# ProPrj_ESP32-S3-DEVKIT_Sensor_Project_20.net
KiCad netlist of a schematic drawn in EasyEDA Pro
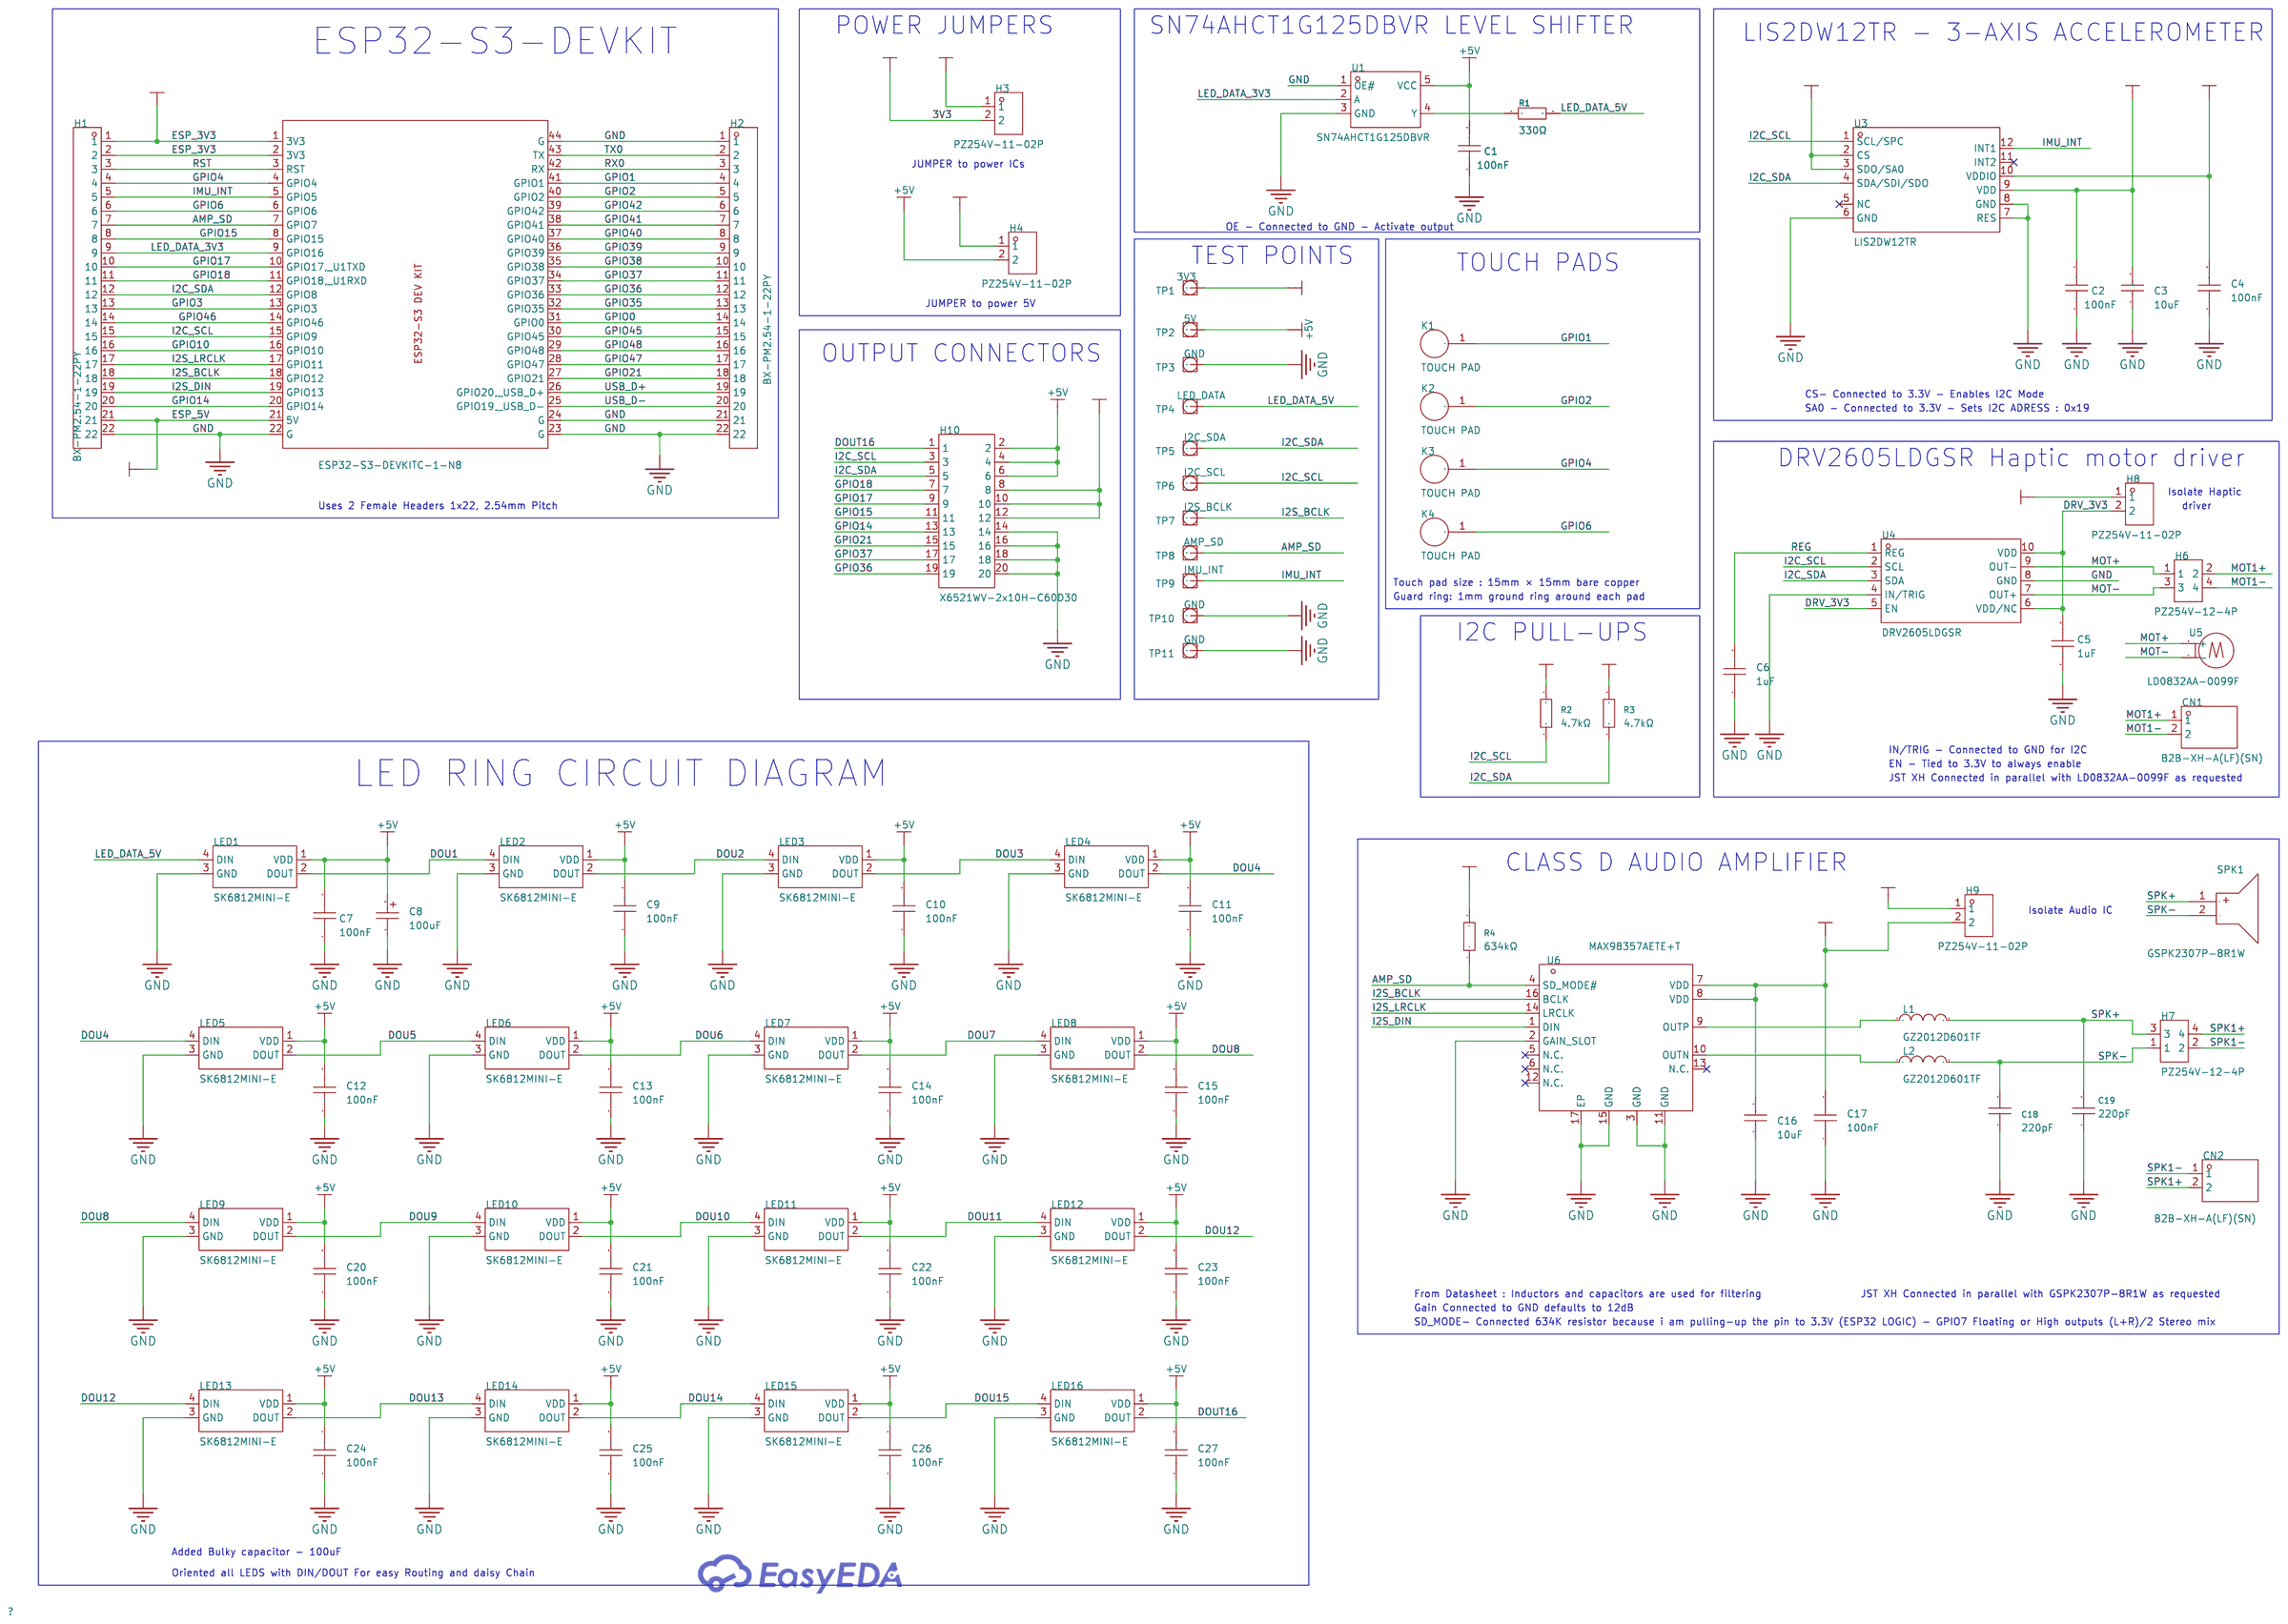
[diagram p0: schematic sheet]

(export (version "E")
  (design (tool "Eeschema 10.0.6"))
  (components
    (comp (ref "C1")
      (value "100nF")
      (footprint "easyedapro:C0402")
      (description "Capacitance:100nF Tolerance:±10% Tolerance:±10% Voltage Rating:16V Temperature Coefficient:X7R")
      (fields
        (field (name "Manufacturer Part") "CL05B104KO5NNNC")
        (field (name "Manufacturer") "SAMSUNG(三星)")
      )
      (libsource (lib "easyedapro") (part "CL05B104KO5NNNC"))
    )
    (comp (ref "C2")
      (value "100nF")
      (footprint "easyedapro:C0402")
      (description "Capacitance:100nF Tolerance:±10% Tolerance:±10% Voltage Rating:16V Temperature Coefficient:X7R")
      (fields
        (field (name "Manufacturer Part") "CL05B104KO5NNNC")
        (field (name "Manufacturer") "SAMSUNG(三星)")
      )
      (libsource (lib "easyedapro") (part "CL05B104KO5NNNC"))
    )
    (comp (ref "C3")
      (value "10uF")
      (footprint "easyedapro:C0402")
      (description "Capacitance:10uF Tolerance:±20% Tolerance:±20% Voltage Rating:6.3V Temperature Coefficient:X5R")
      (fields
        (field (name "Manufacturer Part") "CL05A106MQ5NUNC")
        (field (name "Manufacturer") "SAMSUNG(三星)")
      )
      (libsource (lib "easyedapro") (part "CL05A106MQ5NUNC"))
    )
    (comp (ref "C4")
      (value "100nF")
      (footprint "easyedapro:C0402")
      (description "Capacitance:100nF Tolerance:±10% Tolerance:±10% Voltage Rating:16V Temperature Coefficient:X7R")
      (fields
        (field (name "Manufacturer Part") "CL05B104KO5NNNC")
        (field (name "Manufacturer") "SAMSUNG(三星)")
      )
      (libsource (lib "easyedapro") (part "CL05B104KO5NNNC"))
    )
    (comp (ref "C5")
      (value "1uF")
      (footprint "easyedapro:C0402")
      (description "Capacitance:1uF Tolerance:±10% Tolerance:±10% Voltage Rating:25V Temperature Coefficient:X5R")
      (fields
        (field (name "Manufacturer Part") "CL05A105KA5NQNC")
        (field (name "Manufacturer") "SAMSUNG(三星)")
      )
      (libsource (lib "easyedapro") (part "CL05A105KA5NQNC"))
    )
    (comp (ref "C6")
      (value "1uF")
      (footprint "easyedapro:C0402")
      (description "Capacitance:1uF Tolerance:±10% Tolerance:±10% Voltage Rating:25V Temperature Coefficient:X5R")
      (fields
        (field (name "Manufacturer Part") "CL05A105KA5NQNC")
        (field (name "Manufacturer") "SAMSUNG(三星)")
      )
      (libsource (lib "easyedapro") (part "CL05A105KA5NQNC"))
    )
    (comp (ref "C7")
      (value "100nF")
      (footprint "easyedapro:C0402")
      (description "Capacitance:100nF Tolerance:±10% Tolerance:±10% Voltage Rating:16V Temperature Coefficient:X7R")
      (fields
        (field (name "Manufacturer Part") "CL05B104KO5NNNC")
        (field (name "Manufacturer") "SAMSUNG(三星)")
      )
      (libsource (lib "easyedapro") (part "CL05B104KO5NNNC"))
    )
    (comp (ref "C8")
      (value "100uF")
      (footprint "easyedapro:CASE-B_3528")
      (fields (field (name "Manufacturer Part") "TAJB107M010RNJ") (field (name "Manufacturer") "Kyocera AVX"))
      (libsource (lib "easyedapro") (part "TAJB107M010RNJ"))
    )
    (comp (ref "C9")
      (value "100nF")
      (footprint "easyedapro:C0402")
      (description "Capacitance:100nF Tolerance:±10% Tolerance:±10% Voltage Rating:16V Temperature Coefficient:X7R")
      (fields
        (field (name "Manufacturer Part") "CL05B104KO5NNNC")
        (field (name "Manufacturer") "SAMSUNG(三星)")
      )
      (libsource (lib "easyedapro") (part "CL05B104KO5NNNC"))
    )
    (comp (ref "C10")
      (value "100nF")
      (footprint "easyedapro:C0402")
      (description "Capacitance:100nF Tolerance:±10% Tolerance:±10% Voltage Rating:16V Temperature Coefficient:X7R")
      (fields
        (field (name "Manufacturer Part") "CL05B104KO5NNNC")
        (field (name "Manufacturer") "SAMSUNG(三星)")
      )
      (libsource (lib "easyedapro") (part "CL05B104KO5NNNC"))
    )
    (comp (ref "C11")
      (value "100nF")
      (footprint "easyedapro:C0402")
      (description "Capacitance:100nF Tolerance:±10% Tolerance:±10% Voltage Rating:16V Temperature Coefficient:X7R")
      (fields
        (field (name "Manufacturer Part") "CL05B104KO5NNNC")
        (field (name "Manufacturer") "SAMSUNG(三星)")
      )
      (libsource (lib "easyedapro") (part "CL05B104KO5NNNC"))
    )
    (comp (ref "C12")
      (value "100nF")
      (footprint "easyedapro:C0402")
      (description "Capacitance:100nF Tolerance:±10% Tolerance:±10% Voltage Rating:16V Temperature Coefficient:X7R")
      (fields
        (field (name "Manufacturer Part") "CL05B104KO5NNNC")
        (field (name "Manufacturer") "SAMSUNG(三星)")
      )
      (libsource (lib "easyedapro") (part "CL05B104KO5NNNC"))
    )
    (comp (ref "C13")
      (value "100nF")
      (footprint "easyedapro:C0402")
      (description "Capacitance:100nF Tolerance:±10% Tolerance:±10% Voltage Rating:16V Temperature Coefficient:X7R")
      (fields
        (field (name "Manufacturer Part") "CL05B104KO5NNNC")
        (field (name "Manufacturer") "SAMSUNG(三星)")
      )
      (libsource (lib "easyedapro") (part "CL05B104KO5NNNC"))
    )
    (comp (ref "C14")
      (value "100nF")
      (footprint "easyedapro:C0402")
      (description "Capacitance:100nF Tolerance:±10% Tolerance:±10% Voltage Rating:16V Temperature Coefficient:X7R")
      (fields
        (field (name "Manufacturer Part") "CL05B104KO5NNNC")
        (field (name "Manufacturer") "SAMSUNG(三星)")
      )
      (libsource (lib "easyedapro") (part "CL05B104KO5NNNC"))
    )
    (comp (ref "C15")
      (value "100nF")
      (footprint "easyedapro:C0402")
      (description "Capacitance:100nF Tolerance:±10% Tolerance:±10% Voltage Rating:16V Temperature Coefficient:X7R")
      (fields
        (field (name "Manufacturer Part") "CL05B104KO5NNNC")
        (field (name "Manufacturer") "SAMSUNG(三星)")
      )
      (libsource (lib "easyedapro") (part "CL05B104KO5NNNC"))
    )
    (comp (ref "C16")
      (value "10uF")
      (footprint "easyedapro:C0402")
      (description "Capacitance:10uF Tolerance:±20% Tolerance:±20% Voltage Rating:6.3V Temperature Coefficient:X5R")
      (fields
        (field (name "Manufacturer Part") "CL05A106MQ5NUNC")
        (field (name "Manufacturer") "SAMSUNG(三星)")
      )
      (libsource (lib "easyedapro") (part "CL05A106MQ5NUNC"))
    )
    (comp (ref "C17")
      (value "100nF")
      (footprint "easyedapro:C0402")
      (description "Capacitance:100nF Tolerance:±10% Tolerance:±10% Voltage Rating:16V Temperature Coefficient:X7R")
      (fields
        (field (name "Manufacturer Part") "CL05B104KO5NNNC")
        (field (name "Manufacturer") "SAMSUNG(三星)")
      )
      (libsource (lib "easyedapro") (part "CL05B104KO5NNNC"))
    )
    (comp (ref "C18")
      (value "220pF")
      (footprint "easyedapro:C0603")
      (description "Capacitance:220pF Tolerance:±10% Tolerance:±10% Voltage Rating:50V Temperature Coefficient:X7R")
      (fields
        (field (name "Manufacturer Part") "CL10B221KB8NNNC")
        (field (name "Manufacturer") "SAMSUNG(三星)")
      )
      (libsource (lib "easyedapro") (part "CL10B221KB8NNNC"))
    )
    (comp (ref "C19")
      (value "220pF")
      (footprint "easyedapro:C0603")
      (description "Capacitance:220pF Tolerance:±10% Tolerance:±10% Voltage Rating:50V Temperature Coefficient:X7R")
      (fields
        (field (name "Manufacturer Part") "CL10B221KB8NNNC")
        (field (name "Manufacturer") "SAMSUNG(三星)")
      )
      (libsource (lib "easyedapro") (part "CL10B221KB8NNNC"))
    )
    (comp (ref "C20")
      (value "100nF")
      (footprint "easyedapro:C0402")
      (description "Capacitance:100nF Tolerance:±10% Tolerance:±10% Voltage Rating:16V Temperature Coefficient:X7R")
      (fields
        (field (name "Manufacturer Part") "CL05B104KO5NNNC")
        (field (name "Manufacturer") "SAMSUNG(三星)")
      )
      (libsource (lib "easyedapro") (part "CL05B104KO5NNNC"))
    )
    (comp (ref "C21")
      (value "100nF")
      (footprint "easyedapro:C0402")
      (description "Capacitance:100nF Tolerance:±10% Tolerance:±10% Voltage Rating:16V Temperature Coefficient:X7R")
      (fields
        (field (name "Manufacturer Part") "CL05B104KO5NNNC")
        (field (name "Manufacturer") "SAMSUNG(三星)")
      )
      (libsource (lib "easyedapro") (part "CL05B104KO5NNNC"))
    )
    (comp (ref "C22")
      (value "100nF")
      (footprint "easyedapro:C0402")
      (description "Capacitance:100nF Tolerance:±10% Tolerance:±10% Voltage Rating:16V Temperature Coefficient:X7R")
      (fields
        (field (name "Manufacturer Part") "CL05B104KO5NNNC")
        (field (name "Manufacturer") "SAMSUNG(三星)")
      )
      (libsource (lib "easyedapro") (part "CL05B104KO5NNNC"))
    )
    (comp (ref "C23")
      (value "100nF")
      (footprint "easyedapro:C0402")
      (description "Capacitance:100nF Tolerance:±10% Tolerance:±10% Voltage Rating:16V Temperature Coefficient:X7R")
      (fields
        (field (name "Manufacturer Part") "CL05B104KO5NNNC")
        (field (name "Manufacturer") "SAMSUNG(三星)")
      )
      (libsource (lib "easyedapro") (part "CL05B104KO5NNNC"))
    )
    (comp (ref "C24")
      (value "100nF")
      (footprint "easyedapro:C0402")
      (description "Capacitance:100nF Tolerance:±10% Tolerance:±10% Voltage Rating:16V Temperature Coefficient:X7R")
      (fields
        (field (name "Manufacturer Part") "CL05B104KO5NNNC")
        (field (name "Manufacturer") "SAMSUNG(三星)")
      )
      (libsource (lib "easyedapro") (part "CL05B104KO5NNNC"))
    )
    (comp (ref "C25")
      (value "100nF")
      (footprint "easyedapro:C0402")
      (description "Capacitance:100nF Tolerance:±10% Tolerance:±10% Voltage Rating:16V Temperature Coefficient:X7R")
      (fields
        (field (name "Manufacturer Part") "CL05B104KO5NNNC")
        (field (name "Manufacturer") "SAMSUNG(三星)")
      )
      (libsource (lib "easyedapro") (part "CL05B104KO5NNNC"))
    )
    (comp (ref "C26")
      (value "100nF")
      (footprint "easyedapro:C0402")
      (description "Capacitance:100nF Tolerance:±10% Tolerance:±10% Voltage Rating:16V Temperature Coefficient:X7R")
      (fields
        (field (name "Manufacturer Part") "CL05B104KO5NNNC")
        (field (name "Manufacturer") "SAMSUNG(三星)")
      )
      (libsource (lib "easyedapro") (part "CL05B104KO5NNNC"))
    )
    (comp (ref "C27")
      (value "100nF")
      (footprint "easyedapro:C0402")
      (description "Capacitance:100nF Tolerance:±10% Tolerance:±10% Voltage Rating:16V Temperature Coefficient:X7R")
      (fields
        (field (name "Manufacturer Part") "CL05B104KO5NNNC")
        (field (name "Manufacturer") "SAMSUNG(三星)")
      )
      (libsource (lib "easyedapro") (part "CL05B104KO5NNNC"))
    )
    (comp (ref "CN1")
      (value "B2B-XH-A(LF)(SN)")
      (footprint "easyedapro:CONN-TH_B2B-XH-A-LF-SN")
      (fields (field (name "Manufacturer") "JST"))
      (libsource (lib "easyedapro") (part "B2B-XH-A (LF)(SN)"))
    )
    (comp (ref "CN2")
      (value "B2B-XH-A(LF)(SN)")
      (footprint "easyedapro:CONN-TH_B2B-XH-A-LF-SN")
      (fields (field (name "Manufacturer") "JST"))
      (libsource (lib "easyedapro") (part "B2B-XH-A (LF)(SN)"))
    )
    (comp (ref "H1")
      (value "BX-PM2.54-1-22PY")
      (footprint "easyedapro:HDR-TH_22P-P2.54-V-F")
      (fields (field (name "Manufacturer") "Bossie(博锡)"))
      (libsource (lib "easyedapro") (part "BX-PM2.54-1-22PY"))
    )
    (comp (ref "H2")
      (value "BX-PM2.54-1-22PY")
      (footprint "easyedapro:HDR-TH_22P-P2.54-V-F")
      (fields (field (name "Manufacturer") "Bossie(博锡)"))
      (libsource (lib "easyedapro") (part "BX-PM2.54-1-22PY"))
    )
    (comp (ref "H3")
      (value "PZ254V-11-02P")
      (footprint "easyedapro:HDR-TH_2P-P2.54-V-M")
      (fields (field (name "Manufacturer") "XFCN"))
      (libsource (lib "easyedapro") (part "PZ254V-11-02P"))
    )
    (comp (ref "H4")
      (value "PZ254V-11-02P")
      (footprint "easyedapro:HDR-TH_2P-P2.54-V-M")
      (fields (field (name "Manufacturer") "XFCN"))
      (libsource (lib "easyedapro") (part "PZ254V-11-02P"))
    )
    (comp (ref "H6")
      (value "PZ254V-12-4P")
      (footprint "easyedapro:HDR-TH_4P-P2.54-V-M-R2-C2-S2.54")
      (fields (field (name "Manufacturer") "XFCN(兴飞)"))
      (libsource (lib "easyedapro") (part "PZ254V-12-4P"))
    )
    (comp (ref "H7")
      (value "PZ254V-12-4P")
      (footprint "easyedapro:HDR-TH_4P-P2.54-V-M-R2-C2-S2.54")
      (fields (field (name "Manufacturer") "XFCN(兴飞)"))
      (libsource (lib "easyedapro") (part "PZ254V-12-4P"))
    )
    (comp (ref "H8")
      (value "PZ254V-11-02P")
      (footprint "easyedapro:HDR-TH_2P-P2.54-V-M")
      (fields (field (name "Manufacturer") "XFCN"))
      (libsource (lib "easyedapro") (part "PZ254V-11-02P"))
    )
    (comp (ref "H9")
      (value "PZ254V-11-02P")
      (footprint "easyedapro:HDR-TH_2P-P2.54-V-M")
      (fields (field (name "Manufacturer") "XFCN"))
      (libsource (lib "easyedapro") (part "PZ254V-11-02P"))
    )
    (comp (ref "H10")
      (value "X6521WV-2x10H-C60D30")
      (footprint "easyedapro:HDR-TH_20P-P2.54-V-M-R2-C10-S2.54")
      (fields (field (name "Manufacturer") "XKB Connection(中国星坤)"))
      (libsource (lib "easyedapro") (part "X6521WV-2×10H-C30D60"))
    )
    (comp (ref "K1")
      (value "TOUCH PAD")
      (footprint "easyedapro:TOUCH_PAD")
      (fields (field (name "Manufacturer Part") "Touch"))
      (libsource (lib "easyedapro") (part "TOUCH PAD"))
    )
    (comp (ref "K2")
      (value "TOUCH PAD")
      (footprint "easyedapro:TOUCH_PAD")
      (fields (field (name "Manufacturer Part") "Touch"))
      (libsource (lib "easyedapro") (part "TOUCH PAD"))
    )
    (comp (ref "K3")
      (value "TOUCH PAD")
      (footprint "easyedapro:TOUCH_PAD")
      (fields (field (name "Manufacturer Part") "Touch"))
      (libsource (lib "easyedapro") (part "TOUCH PAD"))
    )
    (comp (ref "K4")
      (value "TOUCH PAD")
      (footprint "easyedapro:TOUCH_PAD")
      (fields (field (name "Manufacturer Part") "Touch"))
      (libsource (lib "easyedapro") (part "TOUCH PAD"))
    )
    (comp (ref "L1")
      (value "GZ2012D601TF")
      (footprint "easyedapro:L0805")
      (fields (field (name "Manufacturer") "Sunlord(顺络)"))
      (libsource (lib "easyedapro") (part "GZ2012D601TF"))
    )
    (comp (ref "L2")
      (value "GZ2012D601TF")
      (footprint "easyedapro:L0805")
      (fields (field (name "Manufacturer") "Sunlord(顺络)"))
      (libsource (lib "easyedapro") (part "GZ2012D601TF"))
    )
    (comp (ref "LED1")
      (value "SK6812MINI-E")
      (footprint "easyedapro:LED-SMD_L3.2-W2.8-LS5.9_SK6812MINI-E")
      (fields (field (name "Manufacturer") "欧思科光电"))
      (libsource (lib "easyedapro") (part "SK6812MINI-E_C5149201"))
    )
    (comp (ref "LED2")
      (value "SK6812MINI-E")
      (footprint "easyedapro:LED-SMD_L3.2-W2.8-LS5.9_SK6812MINI-E")
      (fields (field (name "Manufacturer") "欧思科光电"))
      (libsource (lib "easyedapro") (part "SK6812MINI-E_C5149201"))
    )
    (comp (ref "LED3")
      (value "SK6812MINI-E")
      (footprint "easyedapro:LED-SMD_L3.2-W2.8-LS5.9_SK6812MINI-E")
      (fields (field (name "Manufacturer") "欧思科光电"))
      (libsource (lib "easyedapro") (part "SK6812MINI-E_C5149201"))
    )
    (comp (ref "LED4")
      (value "SK6812MINI-E")
      (footprint "easyedapro:LED-SMD_L3.2-W2.8-LS5.9_SK6812MINI-E")
      (fields (field (name "Manufacturer") "欧思科光电"))
      (libsource (lib "easyedapro") (part "SK6812MINI-E_C5149201"))
    )
    (comp (ref "LED5")
      (value "SK6812MINI-E")
      (footprint "easyedapro:LED-SMD_L3.2-W2.8-LS5.9_SK6812MINI-E")
      (fields (field (name "Manufacturer") "欧思科光电"))
      (libsource (lib "easyedapro") (part "SK6812MINI-E_C5149201"))
    )
    (comp (ref "LED6")
      (value "SK6812MINI-E")
      (footprint "easyedapro:LED-SMD_L3.2-W2.8-LS5.9_SK6812MINI-E")
      (fields (field (name "Manufacturer") "欧思科光电"))
      (libsource (lib "easyedapro") (part "SK6812MINI-E_C5149201"))
    )
    (comp (ref "LED7")
      (value "SK6812MINI-E")
      (footprint "easyedapro:LED-SMD_L3.2-W2.8-LS5.9_SK6812MINI-E")
      (fields (field (name "Manufacturer") "欧思科光电"))
      (libsource (lib "easyedapro") (part "SK6812MINI-E_C5149201"))
    )
    (comp (ref "LED8")
      (value "SK6812MINI-E")
      (footprint "easyedapro:LED-SMD_L3.2-W2.8-LS5.9_SK6812MINI-E")
      (fields (field (name "Manufacturer") "欧思科光电"))
      (libsource (lib "easyedapro") (part "SK6812MINI-E_C5149201"))
    )
    (comp (ref "LED9")
      (value "SK6812MINI-E")
      (footprint "easyedapro:LED-SMD_L3.2-W2.8-LS5.9_SK6812MINI-E")
      (fields (field (name "Manufacturer") "欧思科光电"))
      (libsource (lib "easyedapro") (part "SK6812MINI-E_C5149201"))
    )
    (comp (ref "LED10")
      (value "SK6812MINI-E")
      (footprint "easyedapro:LED-SMD_L3.2-W2.8-LS5.9_SK6812MINI-E")
      (fields (field (name "Manufacturer") "欧思科光电"))
      (libsource (lib "easyedapro") (part "SK6812MINI-E_C5149201"))
    )
    (comp (ref "LED11")
      (value "SK6812MINI-E")
      (footprint "easyedapro:LED-SMD_L3.2-W2.8-LS5.9_SK6812MINI-E")
      (fields (field (name "Manufacturer") "欧思科光电"))
      (libsource (lib "easyedapro") (part "SK6812MINI-E_C5149201"))
    )
    (comp (ref "LED12")
      (value "SK6812MINI-E")
      (footprint "easyedapro:LED-SMD_L3.2-W2.8-LS5.9_SK6812MINI-E")
      (fields (field (name "Manufacturer") "欧思科光电"))
      (libsource (lib "easyedapro") (part "SK6812MINI-E_C5149201"))
    )
    (comp (ref "LED13")
      (value "SK6812MINI-E")
      (footprint "easyedapro:LED-SMD_L3.2-W2.8-LS5.9_SK6812MINI-E")
      (fields (field (name "Manufacturer") "欧思科光电"))
      (libsource (lib "easyedapro") (part "SK6812MINI-E_C5149201"))
    )
    (comp (ref "LED14")
      (value "SK6812MINI-E")
      (footprint "easyedapro:LED-SMD_L3.2-W2.8-LS5.9_SK6812MINI-E")
      (fields (field (name "Manufacturer") "欧思科光电"))
      (libsource (lib "easyedapro") (part "SK6812MINI-E_C5149201"))
    )
    (comp (ref "LED15")
      (value "SK6812MINI-E")
      (footprint "easyedapro:LED-SMD_L3.2-W2.8-LS5.9_SK6812MINI-E")
      (fields (field (name "Manufacturer") "欧思科光电"))
      (libsource (lib "easyedapro") (part "SK6812MINI-E_C5149201"))
    )
    (comp (ref "LED16")
      (value "SK6812MINI-E")
      (footprint "easyedapro:LED-SMD_L3.2-W2.8-LS5.9_SK6812MINI-E")
      (fields (field (name "Manufacturer") "欧思科光电"))
      (libsource (lib "easyedapro") (part "SK6812MINI-E_C5149201"))
    )
    (comp (ref "R1")
      (value "330Ω")
      (footprint "easyedapro:R0402")
      (fields
        (field (name "Manufacturer Part") "0402WGF3300TCE")
        (field (name "Manufacturer") "UNI-ROYAL(厚声)")
      )
      (libsource (lib "easyedapro") (part "0402WGF3300TCE"))
    )
    (comp (ref "R2")
      (value "4.7kΩ")
      (footprint "easyedapro:R0402")
      (fields
        (field (name "Manufacturer Part") "0402WGF4701TCE")
        (field (name "Manufacturer") "UNI-ROYAL(厚声)")
      )
      (libsource (lib "easyedapro") (part "0402WGF4701TCE"))
    )
    (comp (ref "R3")
      (value "4.7kΩ")
      (footprint "easyedapro:R0402")
      (fields
        (field (name "Manufacturer Part") "0402WGF4701TCE")
        (field (name "Manufacturer") "UNI-ROYAL(厚声)")
      )
      (libsource (lib "easyedapro") (part "0402WGF4701TCE"))
    )
    (comp (ref "R4")
      (value "634kΩ")
      (footprint "easyedapro:R0402")
      (fields
        (field (name "Manufacturer Part") "0402WGF6343TCE")
        (field (name "Manufacturer") "UNI-ROYAL(厚声)")
      )
      (libsource (lib "easyedapro") (part "0402WGF6343TCE"))
    )
    (comp (ref "SPK1")
      (value "GSPK2307P-8R1W")
      (footprint "easyedapro:SPK-TH_BD23.0-P10.00-D0.8-L-RD")
      (fields (field (name "Manufacturer") "INGHAi(赢海)"))
      (libsource (lib "easyedapro") (part "GSPK2307P-8R1W"))
    )
    (comp (ref "TP1")
      (value "3V3")
      (footprint "easyedapro:TESTPOINT-TH_BD3.2_1")
      (description "Test Point")
      (libsource (lib "easyedapro") (part "TPoint2"))
    )
    (comp (ref "TP2")
      (value "5V")
      (footprint "easyedapro:TESTPOINT-TH_BD3.2_1")
      (description "Test Point")
      (libsource (lib "easyedapro") (part "TPoint2"))
    )
    (comp (ref "TP3")
      (value "GND")
      (footprint "easyedapro:TESTPOINT-TH_BD3.2_1")
      (description "Test Point")
      (libsource (lib "easyedapro") (part "TPoint2"))
    )
    (comp (ref "TP4")
      (value "LED_DATA")
      (footprint "easyedapro:TESTPOINT-TH_BD3.2_1")
      (description "Test Point")
      (libsource (lib "easyedapro") (part "TPoint2"))
    )
    (comp (ref "TP5")
      (value "I2C_SDA")
      (footprint "easyedapro:TESTPOINT-TH_BD3.2_1")
      (description "Test Point")
      (libsource (lib "easyedapro") (part "TPoint2"))
    )
    (comp (ref "TP6")
      (value "I2C_SCL")
      (footprint "easyedapro:TESTPOINT-TH_BD3.2_1")
      (description "Test Point")
      (libsource (lib "easyedapro") (part "TPoint2"))
    )
    (comp (ref "TP7")
      (value "I2S_BCLK")
      (footprint "easyedapro:TESTPOINT-TH_BD3.2_1")
      (description "Test Point")
      (libsource (lib "easyedapro") (part "TPoint2"))
    )
    (comp (ref "TP8")
      (value "AMP_SD")
      (footprint "easyedapro:TESTPOINT-TH_BD3.2_1")
      (description "Test Point")
      (libsource (lib "easyedapro") (part "TPoint2"))
    )
    (comp (ref "TP9")
      (value "IMU_INT")
      (footprint "easyedapro:TESTPOINT-TH_BD3.2_1")
      (description "Test Point")
      (libsource (lib "easyedapro") (part "TPoint2"))
    )
    (comp (ref "TP10")
      (value "GND")
      (footprint "easyedapro:TESTPOINT-TH_BD3.2_1")
      (description "Test Point")
      (libsource (lib "easyedapro") (part "TPoint2"))
    )
    (comp (ref "TP11")
      (value "GND")
      (footprint "easyedapro:TESTPOINT-TH_BD3.2_1")
      (description "Test Point")
      (libsource (lib "easyedapro") (part "TPoint2"))
    )
    (comp (ref "U1")
      (value "SN74AHCT1G125DBVR")
      (footprint "easyedapro:SOT-23-5_L3.0-W1.7-P0.95-LS2.8-BR")
      (fields (field (name "Manufacturer") "TI(德州仪器)"))
      (libsource (lib "easyedapro") (part "SN74AHCT1G125DBVR"))
    )
    (comp (ref "U2")
      (value "ESP32-S3-DEVKITC-1-N8")
      (footprint "easyedapro:CONN-TH_ESP32-S3-DEVKITC-1U-N8")
      (fields (field (name "Manufacturer") "ESPRESSIF(乐鑫)"))
      (libsource (lib "easyedapro") (part "ESP32-S3-DEVKITC-1-N8"))
    )
    (comp (ref "U3")
      (value "LIS2DW12TR")
      (footprint "easyedapro:LGA-12_L2.0-W2.0-P0.50-BL")
      (fields (field (name "Manufacturer") "ST(意法半导体)"))
      (libsource (lib "easyedapro") (part "LIS2DW12TR"))
    )
    (comp (ref "U4")
      (value "DRV2605LDGSR")
      (footprint "easyedapro:VSSOP-10_L3.0-W3.0-P0.50-LS4.9-BL")
      (fields (field (name "Manufacturer") "TI(德州仪器)"))
      (libsource (lib "easyedapro") (part "DRV2605LDGSR"))
    )
    (comp (ref "U5")
      (value "LD0832AA-0099F")
      (footprint "easyedapro:FL_002")
      (fields (field (name "Manufacturer") "LEADER(立得)"))
      (libsource (lib "easyedapro") (part "LD0832AA-0099F"))
    )
    (comp (ref "U6")
      (value "MAX98357AETE+T")
      (footprint "easyedapro:TQFN-16_L3.0-W3.0-P0.50-BL-EP1.5")
      (fields (field (name "Manufacturer") "ADI(亚德诺)/MAXIM(美信)"))
      (libsource (lib "easyedapro") (part "MAX98357AETE+T"))
    )
  )
  (nets
    (net (code "1") (name "+5V") (class "Default")
      (node (ref "C1") (pin "2") (pinfunction "2_2") (pintype "unspecified"))
      (node (ref "C10") (pin "2") (pinfunction "2_2") (pintype "unspecified"))
      (node (ref "C11") (pin "2") (pinfunction "2_2") (pintype "unspecified"))
      (node (ref "C12") (pin "2") (pinfunction "2_2") (pintype "unspecified"))
      (node (ref "C13") (pin "2") (pinfunction "2_2") (pintype "unspecified"))
      (node (ref "C14") (pin "2") (pinfunction "2_2") (pintype "unspecified"))
      (node (ref "C15") (pin "2") (pinfunction "2_2") (pintype "unspecified"))
      (node (ref "C20") (pin "2") (pinfunction "2_2") (pintype "unspecified"))
      (node (ref "C21") (pin "2") (pinfunction "2_2") (pintype "unspecified"))
      (node (ref "C22") (pin "2") (pinfunction "2_2") (pintype "unspecified"))
      (node (ref "C23") (pin "2") (pinfunction "2_2") (pintype "unspecified"))
      (node (ref "C24") (pin "2") (pinfunction "2_2") (pintype "unspecified"))
      (node (ref "C25") (pin "2") (pinfunction "2_2") (pintype "unspecified"))
      (node (ref "C26") (pin "2") (pinfunction "2_2") (pintype "unspecified"))
      (node (ref "C27") (pin "2") (pinfunction "2_2") (pintype "unspecified"))
      (node (ref "C7") (pin "2") (pinfunction "2_2") (pintype "unspecified"))
      (node (ref "C8") (pin "1") (pinfunction "1_1") (pintype "input"))
      (node (ref "C9") (pin "2") (pinfunction "2_2") (pintype "unspecified"))
      (node (ref "H10") (pin "2") (pinfunction "2_2") (pintype "unspecified"))
      (node (ref "H10") (pin "4") (pinfunction "4_4") (pintype "unspecified"))
      (node (ref "H10") (pin "6") (pinfunction "6_6") (pintype "unspecified"))
      (node (ref "H4") (pin "2") (pinfunction "2_2") (pintype "input"))
      (node (ref "LED1") (pin "1") (pinfunction "VDD_1") (pintype "unspecified"))
      (node (ref "LED10") (pin "1") (pinfunction "VDD_1") (pintype "unspecified"))
      (node (ref "LED11") (pin "1") (pinfunction "VDD_1") (pintype "unspecified"))
      (node (ref "LED12") (pin "1") (pinfunction "VDD_1") (pintype "unspecified"))
      (node (ref "LED13") (pin "1") (pinfunction "VDD_1") (pintype "unspecified"))
      (node (ref "LED14") (pin "1") (pinfunction "VDD_1") (pintype "unspecified"))
      (node (ref "LED15") (pin "1") (pinfunction "VDD_1") (pintype "unspecified"))
      (node (ref "LED16") (pin "1") (pinfunction "VDD_1") (pintype "unspecified"))
      (node (ref "LED2") (pin "1") (pinfunction "VDD_1") (pintype "unspecified"))
      (node (ref "LED3") (pin "1") (pinfunction "VDD_1") (pintype "unspecified"))
      (node (ref "LED4") (pin "1") (pinfunction "VDD_1") (pintype "unspecified"))
      (node (ref "LED5") (pin "1") (pinfunction "VDD_1") (pintype "unspecified"))
      (node (ref "LED6") (pin "1") (pinfunction "VDD_1") (pintype "unspecified"))
      (node (ref "LED7") (pin "1") (pinfunction "VDD_1") (pintype "unspecified"))
      (node (ref "LED8") (pin "1") (pinfunction "VDD_1") (pintype "unspecified"))
      (node (ref "LED9") (pin "1") (pinfunction "VDD_1") (pintype "unspecified"))
      (node (ref "TP2") (pin "1") (pinfunction "1_1") (pintype "input"))
      (node (ref "U1") (pin "5") (pinfunction "VCC_5") (pintype "input"))
    )
    (net (code "2") (name "/AMP_SD") (class "Default")
      (node (ref "H1") (pin "7") (pinfunction "7_7") (pintype "unspecified"))
      (node (ref "R4") (pin "1") (pinfunction "1_1") (pintype "input"))
      (node (ref "TP8") (pin "1") (pinfunction "1_1") (pintype "input"))
      (node (ref "U2") (pin "7") (pinfunction "GPIO7_7") (pintype "unspecified"))
      (node (ref "U6") (pin "4") (pinfunction "SD_MODE#_4") (pintype "unspecified"))
    )
    (net (code "3") (name "/DOU1") (class "Default")
      (node (ref "LED1") (pin "2") (pinfunction "DOUT_2") (pintype "unspecified"))
      (node (ref "LED2") (pin "4") (pinfunction "DIN_4") (pintype "unspecified"))
    )
    (net (code "4") (name "/DOU2") (class "Default")
      (node (ref "LED2") (pin "2") (pinfunction "DOUT_2") (pintype "unspecified"))
      (node (ref "LED3") (pin "4") (pinfunction "DIN_4") (pintype "unspecified"))
    )
    (net (code "5") (name "/DOU3") (class "Default")
      (node (ref "LED3") (pin "2") (pinfunction "DOUT_2") (pintype "unspecified"))
      (node (ref "LED4") (pin "4") (pinfunction "DIN_4") (pintype "unspecified"))
    )
    (net (code "6") (name "/DOU4") (class "Default")
      (node (ref "LED4") (pin "2") (pinfunction "DOUT_2") (pintype "unspecified"))
      (node (ref "LED5") (pin "4") (pinfunction "DIN_4") (pintype "unspecified"))
    )
    (net (code "7") (name "/DOU5") (class "Default")
      (node (ref "LED5") (pin "2") (pinfunction "DOUT_2") (pintype "unspecified"))
      (node (ref "LED6") (pin "4") (pinfunction "DIN_4") (pintype "unspecified"))
    )
    (net (code "8") (name "/DOU6") (class "Default")
      (node (ref "LED6") (pin "2") (pinfunction "DOUT_2") (pintype "unspecified"))
      (node (ref "LED7") (pin "4") (pinfunction "DIN_4") (pintype "unspecified"))
    )
    (net (code "9") (name "/DOU7") (class "Default")
      (node (ref "LED7") (pin "2") (pinfunction "DOUT_2") (pintype "unspecified"))
      (node (ref "LED8") (pin "4") (pinfunction "DIN_4") (pintype "unspecified"))
    )
    (net (code "10") (name "/DOU8") (class "Default")
      (node (ref "LED8") (pin "2") (pinfunction "DOUT_2") (pintype "unspecified"))
      (node (ref "LED9") (pin "4") (pinfunction "DIN_4") (pintype "unspecified"))
    )
    (net (code "11") (name "/DOU9") (class "Default")
      (node (ref "LED10") (pin "4") (pinfunction "DIN_4") (pintype "unspecified"))
      (node (ref "LED9") (pin "2") (pinfunction "DOUT_2") (pintype "unspecified"))
    )
    (net (code "12") (name "/DOU10") (class "Default")
      (node (ref "LED10") (pin "2") (pinfunction "DOUT_2") (pintype "unspecified"))
      (node (ref "LED11") (pin "4") (pinfunction "DIN_4") (pintype "unspecified"))
    )
    (net (code "13") (name "/DOU11") (class "Default")
      (node (ref "LED11") (pin "2") (pinfunction "DOUT_2") (pintype "unspecified"))
      (node (ref "LED12") (pin "4") (pinfunction "DIN_4") (pintype "unspecified"))
    )
    (net (code "14") (name "/DOU12") (class "Default")
      (node (ref "LED12") (pin "2") (pinfunction "DOUT_2") (pintype "unspecified"))
      (node (ref "LED13") (pin "4") (pinfunction "DIN_4") (pintype "unspecified"))
    )
    (net (code "15") (name "/DOU13") (class "Default")
      (node (ref "LED13") (pin "2") (pinfunction "DOUT_2") (pintype "unspecified"))
      (node (ref "LED14") (pin "4") (pinfunction "DIN_4") (pintype "unspecified"))
    )
    (net (code "16") (name "/DOU14") (class "Default")
      (node (ref "LED14") (pin "2") (pinfunction "DOUT_2") (pintype "unspecified"))
      (node (ref "LED15") (pin "4") (pinfunction "DIN_4") (pintype "unspecified"))
    )
    (net (code "17") (name "/DOU15") (class "Default")
      (node (ref "LED15") (pin "2") (pinfunction "DOUT_2") (pintype "unspecified"))
      (node (ref "LED16") (pin "4") (pinfunction "DIN_4") (pintype "unspecified"))
    )
    (net (code "18") (name "/DOUT16") (class "Default")
      (node (ref "H10") (pin "1") (pinfunction "1_1") (pintype "unspecified"))
      (node (ref "LED16") (pin "2") (pinfunction "DOUT_2") (pintype "unspecified"))
    )
    (net (code "19") (name "/DRV_3V3") (class "Default")
      (node (ref "C5") (pin "2") (pinfunction "2_2") (pintype "unspecified"))
      (node (ref "H8") (pin "2") (pinfunction "2_2") (pintype "input"))
      (node (ref "U4") (pin "10") (pinfunction "VDD_10") (pintype "unspecified"))
      (node (ref "U4") (pin "5") (pinfunction "EN_5") (pintype "unspecified"))
      (node (ref "U4") (pin "6") (pinfunction "VDD/NC_6") (pintype "unspecified"))
    )
    (net (code "20") (name "/GPIO0") (class "Default")
      (node (ref "H2") (pin "14") (pinfunction "14_14") (pintype "unspecified"))
      (node (ref "U2") (pin "31") (pinfunction "GPIO0_31") (pintype "unspecified"))
    )
    (net (code "21") (name "/GPIO1") (class "Default")
      (node (ref "H2") (pin "4") (pinfunction "4_4") (pintype "unspecified"))
      (node (ref "K1") (pin "1") (pinfunction "1_1") (pintype "input"))
      (node (ref "U2") (pin "41") (pinfunction "GPIO1_41") (pintype "unspecified"))
    )
    (net (code "22") (name "/GPIO2") (class "Default")
      (node (ref "H2") (pin "5") (pinfunction "5_5") (pintype "unspecified"))
      (node (ref "K2") (pin "1") (pinfunction "1_1") (pintype "input"))
      (node (ref "U2") (pin "40") (pinfunction "GPIO2_40") (pintype "unspecified"))
    )
    (net (code "23") (name "/GPIO3") (class "Default")
      (node (ref "H1") (pin "13") (pinfunction "13_13") (pintype "unspecified"))
      (node (ref "U2") (pin "13") (pinfunction "GPIO3_13") (pintype "unspecified"))
    )
    (net (code "24") (name "/GPIO4") (class "Default")
      (node (ref "H1") (pin "4") (pinfunction "4_4") (pintype "unspecified"))
      (node (ref "K3") (pin "1") (pinfunction "1_1") (pintype "input"))
      (node (ref "U2") (pin "4") (pinfunction "GPIO4_4") (pintype "unspecified"))
    )
    (net (code "25") (name "/GPIO6") (class "Default")
      (node (ref "H1") (pin "6") (pinfunction "6_6") (pintype "unspecified"))
      (node (ref "K4") (pin "1") (pinfunction "1_1") (pintype "input"))
      (node (ref "U2") (pin "6") (pinfunction "GPIO6_6") (pintype "unspecified"))
    )
    (net (code "26") (name "/GPIO10") (class "Default")
      (node (ref "H1") (pin "16") (pinfunction "16_16") (pintype "unspecified"))
      (node (ref "U2") (pin "16") (pinfunction "GPIO10_16") (pintype "unspecified"))
    )
    (net (code "27") (name "/GPIO14") (class "Default")
      (node (ref "H1") (pin "20") (pinfunction "20_20") (pintype "unspecified"))
      (node (ref "H10") (pin "13") (pinfunction "13_13") (pintype "unspecified"))
      (node (ref "U2") (pin "20") (pinfunction "GPIO14_20") (pintype "unspecified"))
    )
    (net (code "28") (name "/GPIO15") (class "Default")
      (node (ref "H1") (pin "8") (pinfunction "8_8") (pintype "unspecified"))
      (node (ref "H10") (pin "11") (pinfunction "11_11") (pintype "unspecified"))
      (node (ref "U2") (pin "8") (pinfunction "GPIO15_8") (pintype "unspecified"))
    )
    (net (code "29") (name "/GPIO17") (class "Default")
      (node (ref "H1") (pin "10") (pinfunction "10_10") (pintype "unspecified"))
      (node (ref "H10") (pin "9") (pinfunction "9_9") (pintype "unspecified"))
      (node (ref "U2") (pin "10") (pinfunction "GPIO17,_U1TXD_10") (pintype "unspecified"))
    )
    (net (code "30") (name "/GPIO18") (class "Default")
      (node (ref "H1") (pin "11") (pinfunction "11_11") (pintype "unspecified"))
      (node (ref "H10") (pin "7") (pinfunction "7_7") (pintype "unspecified"))
      (node (ref "U2") (pin "11") (pinfunction "GPIO18,_U1RXD_11") (pintype "unspecified"))
    )
    (net (code "31") (name "/GPIO21") (class "Default")
      (node (ref "H10") (pin "15") (pinfunction "15_15") (pintype "unspecified"))
      (node (ref "H2") (pin "18") (pinfunction "18_18") (pintype "unspecified"))
      (node (ref "U2") (pin "27") (pinfunction "GPIO21_27") (pintype "unspecified"))
    )
    (net (code "32") (name "/GPIO35") (class "Default")
      (node (ref "H2") (pin "13") (pinfunction "13_13") (pintype "unspecified"))
      (node (ref "U2") (pin "32") (pinfunction "GPIO35_32") (pintype "unspecified"))
    )
    (net (code "33") (name "/GPIO36") (class "Default")
      (node (ref "H10") (pin "19") (pinfunction "19_19") (pintype "unspecified"))
      (node (ref "H2") (pin "12") (pinfunction "12_12") (pintype "unspecified"))
      (node (ref "U2") (pin "33") (pinfunction "GPIO36_33") (pintype "unspecified"))
    )
    (net (code "34") (name "/GPIO37") (class "Default")
      (node (ref "H10") (pin "17") (pinfunction "17_17") (pintype "unspecified"))
      (node (ref "H2") (pin "11") (pinfunction "11_11") (pintype "unspecified"))
      (node (ref "U2") (pin "34") (pinfunction "GPIO37_34") (pintype "unspecified"))
    )
    (net (code "35") (name "/GPIO38") (class "Default")
      (node (ref "H2") (pin "10") (pinfunction "10_10") (pintype "unspecified"))
      (node (ref "U2") (pin "35") (pinfunction "GPIO38_35") (pintype "unspecified"))
    )
    (net (code "36") (name "/GPIO39") (class "Default")
      (node (ref "H2") (pin "9") (pinfunction "9_9") (pintype "unspecified"))
      (node (ref "U2") (pin "36") (pinfunction "GPIO39_36") (pintype "unspecified"))
    )
    (net (code "37") (name "/GPIO40") (class "Default")
      (node (ref "H2") (pin "8") (pinfunction "8_8") (pintype "unspecified"))
      (node (ref "U2") (pin "37") (pinfunction "GPIO40_37") (pintype "unspecified"))
    )
    (net (code "38") (name "/GPIO41") (class "Default")
      (node (ref "H2") (pin "7") (pinfunction "7_7") (pintype "unspecified"))
      (node (ref "U2") (pin "38") (pinfunction "GPIO41_38") (pintype "unspecified"))
    )
    (net (code "39") (name "/GPIO42") (class "Default")
      (node (ref "H2") (pin "6") (pinfunction "6_6") (pintype "unspecified"))
      (node (ref "U2") (pin "39") (pinfunction "GPIO42_39") (pintype "unspecified"))
    )
    (net (code "40") (name "/GPIO45") (class "Default")
      (node (ref "H2") (pin "15") (pinfunction "15_15") (pintype "unspecified"))
      (node (ref "U2") (pin "30") (pinfunction "GPIO45_30") (pintype "unspecified"))
    )
    (net (code "41") (name "/GPIO46") (class "Default")
      (node (ref "H1") (pin "14") (pinfunction "14_14") (pintype "unspecified"))
      (node (ref "U2") (pin "14") (pinfunction "GPIO46_14") (pintype "unspecified"))
    )
    (net (code "42") (name "/GPIO47") (class "Default")
      (node (ref "H2") (pin "17") (pinfunction "17_17") (pintype "unspecified"))
      (node (ref "U2") (pin "28") (pinfunction "GPIO47_28") (pintype "unspecified"))
    )
    (net (code "43") (name "/GPIO48") (class "Default")
      (node (ref "H2") (pin "16") (pinfunction "16_16") (pintype "unspecified"))
      (node (ref "U2") (pin "29") (pinfunction "GPIO48_29") (pintype "unspecified"))
    )
    (net (code "44") (name "/I2C_SCL") (class "Default")
      (node (ref "H1") (pin "15") (pinfunction "15_15") (pintype "unspecified"))
      (node (ref "H10") (pin "3") (pinfunction "3_3") (pintype "unspecified"))
      (node (ref "R2") (pin "1") (pinfunction "1_1") (pintype "input"))
      (node (ref "TP6") (pin "1") (pinfunction "1_1") (pintype "input"))
      (node (ref "U2") (pin "15") (pinfunction "GPIO9_15") (pintype "unspecified"))
      (node (ref "U3") (pin "1") (pinfunction "SCL/SPC_1") (pintype "input"))
      (node (ref "U4") (pin "2") (pinfunction "SCL_2") (pintype "unspecified"))
    )
    (net (code "45") (name "/I2C_SDA") (class "Default")
      (node (ref "H1") (pin "12") (pinfunction "12_12") (pintype "unspecified"))
      (node (ref "H10") (pin "5") (pinfunction "5_5") (pintype "unspecified"))
      (node (ref "R3") (pin "1") (pinfunction "1_1") (pintype "input"))
      (node (ref "TP5") (pin "1") (pinfunction "1_1") (pintype "input"))
      (node (ref "U2") (pin "12") (pinfunction "GPIO8_12") (pintype "unspecified"))
      (node (ref "U3") (pin "4") (pinfunction "SDA/SDI/SDO_4") (pintype "input"))
      (node (ref "U4") (pin "3") (pinfunction "SDA_3") (pintype "unspecified"))
    )
    (net (code "46") (name "/I2S_BCLK") (class "Default")
      (node (ref "H1") (pin "18") (pinfunction "18_18") (pintype "unspecified"))
      (node (ref "TP7") (pin "1") (pinfunction "1_1") (pintype "input"))
      (node (ref "U2") (pin "18") (pinfunction "GPIO12_18") (pintype "unspecified"))
      (node (ref "U6") (pin "16") (pinfunction "BCLK_16") (pintype "unspecified"))
    )
    (net (code "47") (name "/I2S_DIN") (class "Default")
      (node (ref "H1") (pin "19") (pinfunction "19_19") (pintype "unspecified"))
      (node (ref "U2") (pin "19") (pinfunction "GPIO13_19") (pintype "unspecified"))
      (node (ref "U6") (pin "1") (pinfunction "DIN_1") (pintype "unspecified"))
    )
    (net (code "48") (name "/I2S_LRCLK") (class "Default")
      (node (ref "H1") (pin "17") (pinfunction "17_17") (pintype "unspecified"))
      (node (ref "U2") (pin "17") (pinfunction "GPIO11_17") (pintype "unspecified"))
      (node (ref "U6") (pin "14") (pinfunction "LRCLK_14") (pintype "unspecified"))
    )
    (net (code "49") (name "/IMU_INT") (class "Default")
      (node (ref "H1") (pin "5") (pinfunction "5_5") (pintype "unspecified"))
      (node (ref "TP9") (pin "1") (pinfunction "1_1") (pintype "input"))
      (node (ref "U2") (pin "5") (pinfunction "GPIO5_5") (pintype "unspecified"))
      (node (ref "U3") (pin "12") (pinfunction "INT1_12") (pintype "input"))
    )
    (net (code "50") (name "/LED_DATA_3V3") (class "Default")
      (node (ref "H1") (pin "9") (pinfunction "9_9") (pintype "unspecified"))
      (node (ref "U1") (pin "2") (pinfunction "A_2") (pintype "input"))
      (node (ref "U2") (pin "9") (pinfunction "GPIO16_9") (pintype "unspecified"))
    )
    (net (code "51") (name "/LED_DATA_5V") (class "Default")
      (node (ref "LED1") (pin "4") (pinfunction "DIN_4") (pintype "unspecified"))
      (node (ref "R1") (pin "2") (pinfunction "2_2") (pintype "input"))
      (node (ref "TP4") (pin "1") (pinfunction "1_1") (pintype "input"))
    )
    (net (code "52") (name "/MOT+") (class "Default")
      (node (ref "H6") (pin "1") (pinfunction "1_1") (pintype "unspecified"))
      (node (ref "U4") (pin "9") (pinfunction "OUT-_9") (pintype "unspecified"))
      (node (ref "U5") (pin "2") (pinfunction "+_2") (pintype "unspecified"))
    )
    (net (code "53") (name "/MOT-") (class "Default")
      (node (ref "H6") (pin "3") (pinfunction "3_3") (pintype "unspecified"))
      (node (ref "U4") (pin "7") (pinfunction "OUT+_7") (pintype "unspecified"))
      (node (ref "U5") (pin "1") (pinfunction "-_1") (pintype "unspecified"))
    )
    (net (code "54") (name "/MOT1+") (class "Default")
      (node (ref "CN1") (pin "1") (pinfunction "1_1") (pintype "unspecified"))
      (node (ref "H6") (pin "2") (pinfunction "2_2") (pintype "unspecified"))
    )
    (net (code "55") (name "/MOT1-") (class "Default")
      (node (ref "CN1") (pin "2") (pinfunction "2_2") (pintype "unspecified"))
      (node (ref "H6") (pin "4") (pinfunction "4_4") (pintype "unspecified"))
    )
    (net (code "56") (name "/REG") (class "Default")
      (node (ref "C6") (pin "2") (pinfunction "2_2") (pintype "unspecified"))
      (node (ref "U4") (pin "1") (pinfunction "REG_1") (pintype "unspecified"))
    )
    (net (code "57") (name "/RST") (class "Default")
      (node (ref "H1") (pin "3") (pinfunction "3_3") (pintype "unspecified"))
      (node (ref "U2") (pin "3") (pinfunction "RST_3") (pintype "unspecified"))
    )
    (net (code "58") (name "/RX0") (class "Default")
      (node (ref "H2") (pin "3") (pinfunction "3_3") (pintype "unspecified"))
      (node (ref "U2") (pin "42") (pinfunction "RX_42") (pintype "unspecified"))
    )
    (net (code "59") (name "/SPK+") (class "Default")
      (node (ref "C19") (pin "2") (pinfunction "2_2") (pintype "input"))
      (node (ref "H7") (pin "3") (pinfunction "3_3") (pintype "unspecified"))
      (node (ref "L1") (pin "2") (pinfunction "2_2") (pintype "unspecified"))
      (node (ref "SPK1") (pin "1") (pinfunction "+_1") (pintype "unspecified"))
    )
    (net (code "60") (name "/SPK-") (class "Default")
      (node (ref "C18") (pin "2") (pinfunction "2_2") (pintype "input"))
      (node (ref "H7") (pin "1") (pinfunction "1_1") (pintype "unspecified"))
      (node (ref "L2") (pin "2") (pinfunction "2_2") (pintype "unspecified"))
      (node (ref "SPK1") (pin "2") (pinfunction "-_2") (pintype "unspecified"))
    )
    (net (code "61") (name "/SPK1+") (class "Default")
      (node (ref "CN2") (pin "2") (pinfunction "2_2") (pintype "unspecified"))
      (node (ref "H7") (pin "4") (pinfunction "4_4") (pintype "unspecified"))
    )
    (net (code "62") (name "/SPK1-") (class "Default")
      (node (ref "CN2") (pin "1") (pinfunction "1_1") (pintype "unspecified"))
      (node (ref "H7") (pin "2") (pinfunction "2_2") (pintype "unspecified"))
    )
    (net (code "63") (name "/TX0") (class "Default")
      (node (ref "H2") (pin "2") (pinfunction "2_2") (pintype "unspecified"))
      (node (ref "U2") (pin "43") (pinfunction "TX_43") (pintype "unspecified"))
    )
    (net (code "64") (name "/USB_D+") (class "Default")
      (node (ref "H2") (pin "19") (pinfunction "19_19") (pintype "unspecified"))
      (node (ref "U2") (pin "26") (pinfunction "GPIO20,_USB_D+_26") (pintype "unspecified"))
    )
    (net (code "65") (name "/USB_D-") (class "Default")
      (node (ref "H2") (pin "20") (pinfunction "20_20") (pintype "unspecified"))
      (node (ref "U2") (pin "25") (pinfunction "GPIO19,_USB_D-_25") (pintype "unspecified"))
    )
    (net (code "66") (name "3V3") (class "Default")
      (node (ref "C2") (pin "2") (pinfunction "2_2") (pintype "unspecified"))
      (node (ref "C3") (pin "2") (pinfunction "2_2") (pintype "input"))
      (node (ref "C4") (pin "2") (pinfunction "2_2") (pintype "unspecified"))
      (node (ref "H10") (pin "10") (pinfunction "10_10") (pintype "unspecified"))
      (node (ref "H10") (pin "12") (pinfunction "12_12") (pintype "unspecified"))
      (node (ref "H10") (pin "8") (pinfunction "8_8") (pintype "unspecified"))
      (node (ref "H3") (pin "2") (pinfunction "2_2") (pintype "input"))
      (node (ref "H8") (pin "1") (pinfunction "1_1") (pintype "input"))
      (node (ref "R2") (pin "2") (pinfunction "2_2") (pintype "input"))
      (node (ref "R3") (pin "2") (pinfunction "2_2") (pintype "input"))
      (node (ref "R4") (pin "2") (pinfunction "2_2") (pintype "input"))
      (node (ref "TP1") (pin "1") (pinfunction "1_1") (pintype "input"))
      (node (ref "U3") (pin "10") (pinfunction "VDDIO_10") (pintype "input"))
      (node (ref "U3") (pin "2") (pinfunction "CS_2") (pintype "input"))
      (node (ref "U3") (pin "3") (pinfunction "SDO/SA0_3") (pintype "input"))
      (node (ref "U3") (pin "9") (pinfunction "VDD_9") (pintype "input"))
    )
    (net (code "67") (name "ESP_3V3") (class "Default")
      (node (ref "H1") (pin "1") (pinfunction "1_1") (pintype "unspecified"))
      (node (ref "H1") (pin "2") (pinfunction "2_2") (pintype "unspecified"))
      (node (ref "H3") (pin "1") (pinfunction "1_1") (pintype "input"))
      (node (ref "U2") (pin "1") (pinfunction "3V3_1") (pintype "unspecified"))
      (node (ref "U2") (pin "2") (pinfunction "3V3_2") (pintype "unspecified"))
    )
    (net (code "68") (name "ESP_5V") (class "Default")
      (node (ref "H1") (pin "21") (pinfunction "21_21") (pintype "unspecified"))
      (node (ref "H4") (pin "1") (pinfunction "1_1") (pintype "input"))
      (node (ref "H9") (pin "1") (pinfunction "1_1") (pintype "input"))
      (node (ref "U2") (pin "21") (pinfunction "5V_21") (pintype "unspecified"))
    )
    (net (code "69") (name "GND") (class "Default")
      (node (ref "C1") (pin "1") (pinfunction "1_1") (pintype "unspecified"))
      (node (ref "C10") (pin "1") (pinfunction "1_1") (pintype "unspecified"))
      (node (ref "C11") (pin "1") (pinfunction "1_1") (pintype "unspecified"))
      (node (ref "C12") (pin "1") (pinfunction "1_1") (pintype "unspecified"))
      (node (ref "C13") (pin "1") (pinfunction "1_1") (pintype "unspecified"))
      (node (ref "C14") (pin "1") (pinfunction "1_1") (pintype "unspecified"))
      (node (ref "C15") (pin "1") (pinfunction "1_1") (pintype "unspecified"))
      (node (ref "C16") (pin "1") (pinfunction "1_1") (pintype "input"))
      (node (ref "C17") (pin "1") (pinfunction "1_1") (pintype "unspecified"))
      (node (ref "C18") (pin "1") (pinfunction "1_1") (pintype "input"))
      (node (ref "C19") (pin "1") (pinfunction "1_1") (pintype "input"))
      (node (ref "C2") (pin "1") (pinfunction "1_1") (pintype "unspecified"))
      (node (ref "C20") (pin "1") (pinfunction "1_1") (pintype "unspecified"))
      (node (ref "C21") (pin "1") (pinfunction "1_1") (pintype "unspecified"))
      (node (ref "C22") (pin "1") (pinfunction "1_1") (pintype "unspecified"))
      (node (ref "C23") (pin "1") (pinfunction "1_1") (pintype "unspecified"))
      (node (ref "C24") (pin "1") (pinfunction "1_1") (pintype "unspecified"))
      (node (ref "C25") (pin "1") (pinfunction "1_1") (pintype "unspecified"))
      (node (ref "C26") (pin "1") (pinfunction "1_1") (pintype "unspecified"))
      (node (ref "C27") (pin "1") (pinfunction "1_1") (pintype "unspecified"))
      (node (ref "C3") (pin "1") (pinfunction "1_1") (pintype "input"))
      (node (ref "C4") (pin "1") (pinfunction "1_1") (pintype "unspecified"))
      (node (ref "C5") (pin "1") (pinfunction "1_1") (pintype "unspecified"))
      (node (ref "C6") (pin "1") (pinfunction "1_1") (pintype "unspecified"))
      (node (ref "C7") (pin "1") (pinfunction "1_1") (pintype "unspecified"))
      (node (ref "C8") (pin "2") (pinfunction "2_2") (pintype "input"))
      (node (ref "C9") (pin "1") (pinfunction "1_1") (pintype "unspecified"))
      (node (ref "H1") (pin "22") (pinfunction "22_22") (pintype "unspecified"))
      (node (ref "H10") (pin "14") (pinfunction "14_14") (pintype "unspecified"))
      (node (ref "H10") (pin "16") (pinfunction "16_16") (pintype "unspecified"))
      (node (ref "H10") (pin "18") (pinfunction "18_18") (pintype "unspecified"))
      (node (ref "H10") (pin "20") (pinfunction "20_20") (pintype "unspecified"))
      (node (ref "H2") (pin "1") (pinfunction "1_1") (pintype "unspecified"))
      (node (ref "H2") (pin "21") (pinfunction "21_21") (pintype "unspecified"))
      (node (ref "H2") (pin "22") (pinfunction "22_22") (pintype "unspecified"))
      (node (ref "LED1") (pin "3") (pinfunction "GND_3") (pintype "unspecified"))
      (node (ref "LED10") (pin "3") (pinfunction "GND_3") (pintype "unspecified"))
      (node (ref "LED11") (pin "3") (pinfunction "GND_3") (pintype "unspecified"))
      (node (ref "LED12") (pin "3") (pinfunction "GND_3") (pintype "unspecified"))
      (node (ref "LED13") (pin "3") (pinfunction "GND_3") (pintype "unspecified"))
      (node (ref "LED14") (pin "3") (pinfunction "GND_3") (pintype "unspecified"))
      (node (ref "LED15") (pin "3") (pinfunction "GND_3") (pintype "unspecified"))
      (node (ref "LED16") (pin "3") (pinfunction "GND_3") (pintype "unspecified"))
      (node (ref "LED2") (pin "3") (pinfunction "GND_3") (pintype "unspecified"))
      (node (ref "LED3") (pin "3") (pinfunction "GND_3") (pintype "unspecified"))
      (node (ref "LED4") (pin "3") (pinfunction "GND_3") (pintype "unspecified"))
      (node (ref "LED5") (pin "3") (pinfunction "GND_3") (pintype "unspecified"))
      (node (ref "LED6") (pin "3") (pinfunction "GND_3") (pintype "unspecified"))
      (node (ref "LED7") (pin "3") (pinfunction "GND_3") (pintype "unspecified"))
      (node (ref "LED8") (pin "3") (pinfunction "GND_3") (pintype "unspecified"))
      (node (ref "LED9") (pin "3") (pinfunction "GND_3") (pintype "unspecified"))
      (node (ref "TP10") (pin "1") (pinfunction "1_1") (pintype "input"))
      (node (ref "TP11") (pin "1") (pinfunction "1_1") (pintype "input"))
      (node (ref "TP3") (pin "1") (pinfunction "1_1") (pintype "input"))
      (node (ref "U1") (pin "1") (pinfunction "OE#_1") (pintype "input"))
      (node (ref "U1") (pin "3") (pinfunction "GND_3") (pintype "input"))
      (node (ref "U2") (pin "22") (pinfunction "G_22") (pintype "unspecified"))
      (node (ref "U2") (pin "23") (pinfunction "G_23") (pintype "unspecified"))
      (node (ref "U2") (pin "24") (pinfunction "G_24") (pintype "unspecified"))
      (node (ref "U2") (pin "44") (pinfunction "G_44") (pintype "unspecified"))
      (node (ref "U3") (pin "6") (pinfunction "GND_6") (pintype "input"))
      (node (ref "U3") (pin "7") (pinfunction "RES_7") (pintype "input"))
      (node (ref "U3") (pin "8") (pinfunction "GND_8") (pintype "input"))
      (node (ref "U4") (pin "4") (pinfunction "IN/TRIG_4") (pintype "unspecified"))
      (node (ref "U4") (pin "8") (pinfunction "GND_8") (pintype "unspecified"))
      (node (ref "U6") (pin "11") (pinfunction "GND_11") (pintype "unspecified"))
      (node (ref "U6") (pin "15") (pinfunction "GND_15") (pintype "unspecified"))
      (node (ref "U6") (pin "17") (pinfunction "EP_17") (pintype "unspecified"))
      (node (ref "U6") (pin "2") (pinfunction "GAIN_SLOT_2") (pintype "unspecified"))
      (node (ref "U6") (pin "3") (pinfunction "GND_3") (pintype "unspecified"))
    )
    (net (code "70") (name "Net-(U1-Y)") (class "Default")
      (node (ref "R1") (pin "1") (pinfunction "1_1") (pintype "input"))
      (node (ref "U1") (pin "4") (pinfunction "Y_4") (pintype "input"))
    )
    (net (code "71") (name "Net-(U6-OUTN)") (class "Default")
      (node (ref "L2") (pin "1") (pinfunction "1_1") (pintype "unspecified"))
      (node (ref "U6") (pin "10") (pinfunction "OUTN_10") (pintype "unspecified"))
    )
    (net (code "72") (name "Net-(U6-OUTP)") (class "Default")
      (node (ref "L1") (pin "1") (pinfunction "1_1") (pintype "unspecified"))
      (node (ref "U6") (pin "9") (pinfunction "OUTP_9") (pintype "unspecified"))
    )
    (net (code "73") (name "VCC_5V") (class "Default")
      (node (ref "C16") (pin "2") (pinfunction "2_2") (pintype "input"))
      (node (ref "C17") (pin "2") (pinfunction "2_2") (pintype "unspecified"))
      (node (ref "H9") (pin "2") (pinfunction "2_2") (pintype "input"))
      (node (ref "U6") (pin "7") (pinfunction "VDD_7") (pintype "unspecified"))
      (node (ref "U6") (pin "8") (pinfunction "VDD_8") (pintype "unspecified"))
    )
    (net (code "74") (name "unconnected-(U3-INT2-Pad11)") (class "Default")
      (node (ref "U3") (pin "11") (pinfunction "INT2_11") (pintype "input+no_connect"))
    )
    (net (code "75") (name "unconnected-(U3-NC-Pad5)") (class "Default")
      (node (ref "U3") (pin "5") (pinfunction "NC_5") (pintype "input+no_connect"))
    )
    (net (code "76") (name "unconnected-(U6-N.C.-Pad5)") (class "Default")
      (node (ref "U6") (pin "5") (pinfunction "N.C._5") (pintype "unspecified+no_connect"))
    )
    (net (code "77") (name "unconnected-(U6-N.C.-Pad6)") (class "Default")
      (node (ref "U6") (pin "6") (pinfunction "N.C._6") (pintype "unspecified+no_connect"))
    )
    (net (code "78") (name "unconnected-(U6-N.C.-Pad12)") (class "Default")
      (node (ref "U6") (pin "12") (pinfunction "N.C._12") (pintype "unspecified+no_connect"))
    )
    (net (code "79") (name "unconnected-(U6-N.C.-Pad13)") (class "Default")
      (node (ref "U6") (pin "13") (pinfunction "N.C._13") (pintype "unspecified+no_connect"))
    )
  )
)
